# front_ultrasonic_radar.net
KiCad netlist of a schematic drawn in Altium Designer
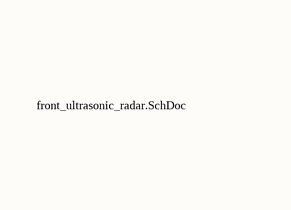
[diagram p0: front_ultrasonic_radar.SchDoc, left]
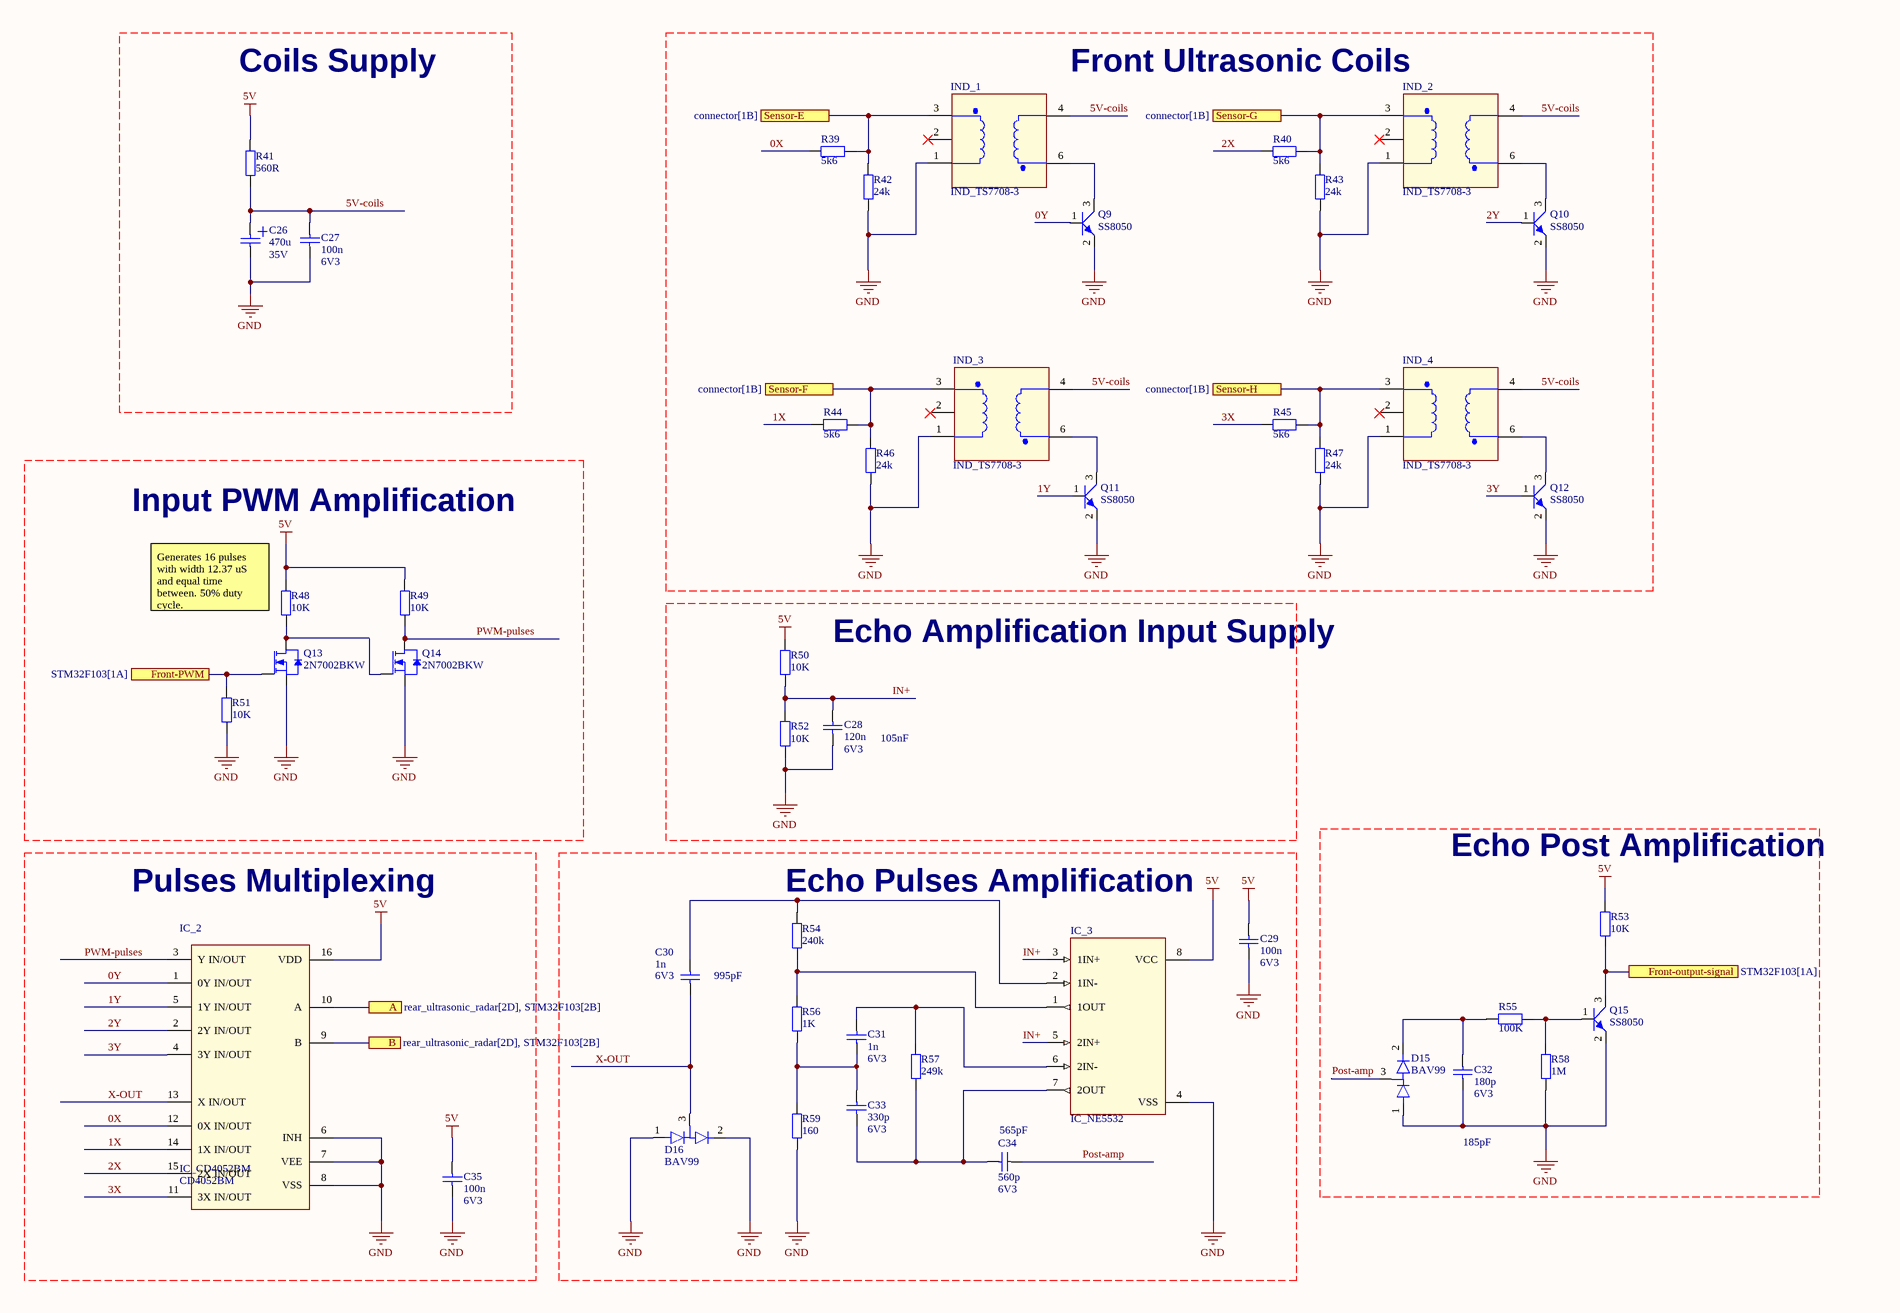
[diagram p1: front_ultrasonic_radar.SchDoc, right]

(export (version "E")
  (design (tool "Eeschema 10.0.6"))
  (components
    (comp (ref "C26")
      (value "CAP_POL")
      (footprint "CAP_Panasonic_EEE-FK1V471SP")
      (description "Aluminium Electrolytic Capacitors - SMD 35volts 470uF SMD AEC-Q200 Reflow Only")
      (fields
        (field (name "VALUE1") "470u")
        (field (name "VALUE2") "35V")
        (field (name "MANUFACTURER") "Panasonic")
      )
      (libsource (lib "DSW_Lib") (part "CAP_POL"))
    )
    (comp (ref "C27")
      (value "CAP")
      (footprint "CAPC2012X88N")
      (description "X7R 10% 0805")
      (fields
        (field (name "VALUE1") "100n")
        (field (name "VALUE2") "6V3")
        (field (name "MANUFACTURER") "KEMET")
      )
      (libsource (lib "DSW_Lib") (part "CAP"))
    )
    (comp (ref "C28")
      (value "CAP")
      (footprint "CAPC2012X88N")
      (description "X7R 10% 0805")
      (fields
        (field (name "VALUE1") "120n")
        (field (name "VALUE2") "6V3")
        (field (name "MANUFACTURER") "KEMET")
      )
      (libsource (lib "DSW_Lib") (part "CAP"))
    )
    (comp (ref "C29")
      (value "CAP")
      (footprint "CAPC2012X88N")
      (description "X7R 10% 0805")
      (fields
        (field (name "VALUE1") "100n")
        (field (name "VALUE2") "6V3")
        (field (name "MANUFACTURER") "KEMET")
      )
      (libsource (lib "DSW_Lib") (part "CAP"))
    )
    (comp (ref "C30")
      (value "CAP")
      (footprint "CAPC2012X88N")
      (description "X7R 10% 0805")
      (fields
        (field (name "VALUE1") "1n")
        (field (name "VALUE2") "6V3")
        (field (name "MANUFACTURER") "KEMET")
      )
      (libsource (lib "DSW_Lib") (part "CAP"))
    )
    (comp (ref "C31")
      (value "CAP")
      (footprint "CAPC2012X88N")
      (description "X7R 10% 0805")
      (fields
        (field (name "VALUE1") "1n")
        (field (name "VALUE2") "6V3")
        (field (name "MANUFACTURER") "KEMET")
      )
      (libsource (lib "DSW_Lib") (part "CAP"))
    )
    (comp (ref "C32")
      (value "CAP")
      (footprint "CAPC2012X88N")
      (description "X7R 10% 0805")
      (fields
        (field (name "VALUE1") "180p")
        (field (name "VALUE2") "6V3")
        (field (name "MANUFACTURER") "KEMET")
      )
      (libsource (lib "DSW_Lib") (part "CAP"))
    )
    (comp (ref "C33")
      (value "CAP")
      (footprint "CAPC2012X88N")
      (description "X7R 10% 0805")
      (fields
        (field (name "VALUE1") "330p")
        (field (name "VALUE2") "6V3")
        (field (name "MANUFACTURER") "KEMET")
      )
      (libsource (lib "DSW_Lib") (part "CAP"))
    )
    (comp (ref "C34")
      (value "CAP")
      (footprint "CAPC2012X88N")
      (description "X7R 10% 0805")
      (fields
        (field (name "VALUE1") "560p")
        (field (name "VALUE2") "6V3")
        (field (name "MANUFACTURER") "KEMET")
      )
      (libsource (lib "DSW_Lib") (part "CAP"))
    )
    (comp (ref "C35")
      (value "CAP")
      (footprint "CAPC2012X88N")
      (description "X7R 10% 0805")
      (fields
        (field (name "VALUE1") "100n")
        (field (name "VALUE2") "6V3")
        (field (name "MANUFACTURER") "KEMET")
      )
      (libsource (lib "DSW_Lib") (part "CAP"))
    )
    (comp (ref "D15")
      (value "High-speed double diode")
      (footprint "DIO_BAV99-SOT23")
      (fields (field (name "VALUE1") "BAV99") (field (name "MANUFACTURER") "Philips"))
      (libsource (lib "DSW_Lib") (part "DIO_BAV99"))
    )
    (comp (ref "D16")
      (value "High-speed double diode")
      (footprint "DIO_BAV99-SOT23")
      (fields (field (name "VALUE1") "BAV99") (field (name "MANUFACTURER") "Philips"))
      (libsource (lib "DSW_Lib") (part "DIO_BAV99"))
    )
    (comp (ref "IC_2")
      (value "IC_CD4052BM")
      (footprint "SOP-16")
      (description "Dual 4-Channel Analog Multiplexer/Demultiplexer")
      (fields (field (name "VALUE1") "CD4052BM") (field (name "MANUFACTURER") "Texas Instruments"))
      (libsource (lib "DSW_Lib") (part "IC_CD4052BM"))
    )
    (comp (ref "IC_3")
      (value "IC_NE5532")
      (description "Dual low-noise operational amplifier ")
      (libsource (lib "IC_NE5532") (part "IC_NE5532"))
    )
    (comp (ref "IND_1")
      (value "IND_TS7708-3")
      (description "12times Amplifying Transformer,IFT Inductors for Ultrasonic Sensors")
      (libsource (lib "IND_TS7708-3") (part "IND_TS7708-3"))
    )
    (comp (ref "IND_2")
      (value "IND_TS7708-3")
      (description "12times Amplifying Transformer,IFT Inductors for Ultrasonic Sensors")
      (libsource (lib "IND_TS7708-3") (part "IND_TS7708-3"))
    )
    (comp (ref "IND_3")
      (value "IND_TS7708-3")
      (description "12times Amplifying Transformer,IFT Inductors for Ultrasonic Sensors")
      (libsource (lib "IND_TS7708-3") (part "IND_TS7708-3"))
    )
    (comp (ref "IND_4")
      (value "IND_TS7708-3")
      (description "12times Amplifying Transformer,IFT Inductors for Ultrasonic Sensors")
      (libsource (lib "IND_TS7708-3") (part "IND_TS7708-3"))
    )
    (comp (ref "Q9")
      (value "TRS_NPN_123")
      (footprint "SOT23")
      (description "Bipolar Transistors - BJT NPN TRANSISTOR 1.5A 40V")
      (fields (field (name "VALUE1") "SS8050") (field (name "MANUFACTURER") "KooChin"))
      (libsource (lib "DSW_Lib") (part "TRS_NPN_123"))
    )
    (comp (ref "Q10")
      (value "TRS_NPN_123")
      (footprint "SOT23")
      (description "Bipolar Transistors - BJT NPN TRANSISTOR 1.5A 40V")
      (fields (field (name "VALUE1") "SS8050") (field (name "MANUFACTURER") "KooChin"))
      (libsource (lib "DSW_Lib") (part "TRS_NPN_123"))
    )
    (comp (ref "Q11")
      (value "TRS_NPN_123")
      (footprint "SOT23")
      (description "Bipolar Transistors - BJT NPN TRANSISTOR 1.5A 40V")
      (fields (field (name "VALUE1") "SS8050") (field (name "MANUFACTURER") "KooChin"))
      (libsource (lib "DSW_Lib") (part "TRS_NPN_123"))
    )
    (comp (ref "Q12")
      (value "TRS_NPN_123")
      (footprint "SOT23")
      (description "Bipolar Transistors - BJT NPN TRANSISTOR 1.5A 40V")
      (fields (field (name "VALUE1") "SS8050") (field (name "MANUFACTURER") "KooChin"))
      (libsource (lib "DSW_Lib") (part "TRS_NPN_123"))
    )
    (comp (ref "Q13")
      (value "TRS_FETN_123")
      (footprint "SOT65P210X110-3N")
      (description "NXP - 2N7002BKW - MOSFET, N CH, 60V, 0.31A, SOT323")
      (fields (field (name "VALUE1") "2N7002BKW") (field (name "MANUFACTURER") "NXP"))
      (libsource (lib "DSW_Lib") (part "TRS_FETN_123"))
    )
    (comp (ref "Q14")
      (value "TRS_FETN_123")
      (footprint "SOT65P210X110-3N")
      (description "NXP - 2N7002BKW - MOSFET, N CH, 60V, 0.31A, SOT323")
      (fields (field (name "VALUE1") "2N7002BKW") (field (name "MANUFACTURER") "NXP"))
      (libsource (lib "DSW_Lib") (part "TRS_FETN_123"))
    )
    (comp (ref "Q15")
      (value "TRS_NPN_123")
      (footprint "SOT23")
      (description "Bipolar Transistors - BJT NPN TRANSISTOR 1.5A 40V")
      (fields (field (name "VALUE1") "SS8050") (field (name "MANUFACTURER") "KooChin"))
      (libsource (lib "DSW_Lib") (part "TRS_NPN_123"))
    )
    (comp (ref "R39")
      (value "RES")
      (footprint "RESC2012X60N")
      (description "RESISTOR, 0805, 5k6, 1%, SMD")
      (fields (field (name "VALUE1") "5k6") (field (name "MANUFACTURER") "Yageo"))
      (libsource (lib "") (part "RES_1"))
    )
    (comp (ref "R40")
      (value "RES")
      (footprint "RESC2012X60N")
      (description "RESISTOR, 0805, 5k6, 1%, SMD")
      (fields (field (name "VALUE1") "5k6") (field (name "MANUFACTURER") "Yageo"))
      (libsource (lib "") (part "RES_1"))
    )
    (comp (ref "R41")
      (value "RES")
      (footprint "RESC2012X60N")
      (description "RESISTOR, 0805, 560R, 1%, SMD")
      (fields (field (name "VALUE1") "560R") (field (name "MANUFACTURER") "Yageo"))
      (libsource (lib "DSW_Lib") (part "RES"))
    )
    (comp (ref "R42")
      (value "RES")
      (footprint "RESC2012X60N")
      (description "RESISTOR, 0805, 24k, 1%, SMD")
      (fields (field (name "VALUE1") "24k") (field (name "MANUFACTURER") "Yageo"))
      (libsource (lib "DSW_Lib") (part "RES"))
    )
    (comp (ref "R43")
      (value "RES")
      (footprint "RESC2012X60N")
      (description "RESISTOR, 0805, 24k, 1%, SMD")
      (fields (field (name "VALUE1") "24k") (field (name "MANUFACTURER") "Yageo"))
      (libsource (lib "DSW_Lib") (part "RES"))
    )
    (comp (ref "R44")
      (value "RES")
      (footprint "RESC2012X60N")
      (description "RESISTOR, 0805, 5k6, 1%, SMD")
      (fields (field (name "VALUE1") "5k6") (field (name "MANUFACTURER") "Yageo"))
      (libsource (lib "") (part "RES_1"))
    )
    (comp (ref "R45")
      (value "RES")
      (footprint "RESC2012X60N")
      (description "RESISTOR, 0805, 5k6, 1%, SMD")
      (fields (field (name "VALUE1") "5k6") (field (name "MANUFACTURER") "Yageo"))
      (libsource (lib "") (part "RES_1"))
    )
    (comp (ref "R46")
      (value "RES")
      (footprint "RESC2012X60N")
      (description "RESISTOR, 0805, 24k, 1%, SMD")
      (fields (field (name "VALUE1") "24k") (field (name "MANUFACTURER") "Yageo"))
      (libsource (lib "DSW_Lib") (part "RES"))
    )
    (comp (ref "R47")
      (value "RES")
      (footprint "RESC2012X60N")
      (description "RESISTOR, 0805, 24k, 1%, SMD")
      (fields (field (name "VALUE1") "24k") (field (name "MANUFACTURER") "Yageo"))
      (libsource (lib "DSW_Lib") (part "RES"))
    )
    (comp (ref "R48")
      (value "RES")
      (footprint "RESC2012X60N")
      (description "RESISTOR, 0805, 10K, 1%, SMD")
      (fields (field (name "VALUE1") "10K") (field (name "MANUFACTURER") "Yageo"))
      (libsource (lib "DSW_Lib") (part "RES"))
    )
    (comp (ref "R49")
      (value "RES")
      (footprint "RESC2012X60N")
      (description "RESISTOR, 0805, 10K, 1%, SMD")
      (fields (field (name "VALUE1") "10K") (field (name "MANUFACTURER") "Yageo"))
      (libsource (lib "DSW_Lib") (part "RES"))
    )
    (comp (ref "R50")
      (value "RES")
      (footprint "RESC2012X60N")
      (description "RESISTOR, 0805, 10K, 1%, SMD")
      (fields (field (name "VALUE1") "10K") (field (name "MANUFACTURER") "Yageo"))
      (libsource (lib "") (part "RES_2"))
    )
    (comp (ref "R51")
      (value "RES")
      (footprint "RESC2012X60N")
      (description "RESISTOR, 0805, 10K, 1%, SMD")
      (fields (field (name "VALUE1") "10K") (field (name "MANUFACTURER") "Yageo"))
      (libsource (lib "DSW_Lib") (part "RES"))
    )
    (comp (ref "R52")
      (value "RES")
      (footprint "RESC2012X60N")
      (description "RESISTOR, 0805, 10K, 1%, SMD")
      (fields (field (name "VALUE1") "10K") (field (name "MANUFACTURER") "Yageo"))
      (libsource (lib "DSW_Lib") (part "RES"))
    )
    (comp (ref "R53")
      (value "RES")
      (footprint "RESC2012X60N")
      (description "RESISTOR, 0805, 10K, 1%, SMD")
      (fields (field (name "VALUE1") "10K") (field (name "MANUFACTURER") "Yageo"))
      (libsource (lib "DSW_Lib") (part "RES"))
    )
    (comp (ref "R54")
      (value "RES")
      (footprint "RESC2012X60N")
      (description "RESISTOR, 0805, 240k, 1%, SMD")
      (fields (field (name "VALUE1") "240k") (field (name "MANUFACTURER") "Yageo"))
      (libsource (lib "") (part "RES_2"))
    )
    (comp (ref "R55")
      (value "RES")
      (footprint "RESC2012X60N")
      (description "RESISTOR, 0805, 100K, 1%, SMD")
      (fields (field (name "VALUE1") "100K") (field (name "MANUFACTURER") "Yageo"))
      (libsource (lib "") (part "RES_3"))
    )
    (comp (ref "R56")
      (value "RES")
      (footprint "RESC2012X60N")
      (description "RESISTOR, 0805, 1K, 1%, SMD")
      (fields (field (name "VALUE1") "1K") (field (name "MANUFACTURER") "Yageo"))
      (libsource (lib "DSW_Lib") (part "RES"))
    )
    (comp (ref "R57")
      (value "RES")
      (footprint "RESC2012X60N")
      (description "RESISTOR, 0805, 249k, 1%, SMD")
      (fields (field (name "VALUE1") "249k") (field (name "MANUFACTURER") "Yageo"))
      (libsource (lib "") (part "RES_2"))
    )
    (comp (ref "R58")
      (value "RES")
      (footprint "RESC2012X60N")
      (description "RESISTOR, 0805, 1M, 1%, SMD")
      (fields (field (name "VALUE1") "1M") (field (name "MANUFACTURER") "Yageo"))
      (libsource (lib "DSW_Lib") (part "RES"))
    )
    (comp (ref "R59")
      (value "RES")
      (footprint "RESC2012X60N")
      (description "RESISTOR, 0805, 160, 1%, SMD")
      (fields (field (name "VALUE1") "160") (field (name "MANUFACTURER") "Yageo"))
      (libsource (lib "DSW_Lib") (part "RES"))
    )
  )
  (nets
    (net (code "1") (name "/0X") (class "Default")
      (node (ref "IC_2") (pin "12") (pinfunction "0X_IN/OUT_12") (pintype "passive"))
      (node (ref "R39") (pin "2") (pinfunction "2_2") (pintype "passive"))
    )
    (net (code "2") (name "/0Y") (class "Default")
      (node (ref "IC_2") (pin "1") (pinfunction "0Y_IN/OUT_1") (pintype "passive"))
      (node (ref "Q9") (pin "1") (pinfunction "B_1") (pintype "passive"))
    )
    (net (code "3") (name "/1X") (class "Default")
      (node (ref "IC_2") (pin "14") (pinfunction "1X_IN/OUT_14") (pintype "passive"))
      (node (ref "R44") (pin "2") (pinfunction "2_2") (pintype "passive"))
    )
    (net (code "4") (name "/1Y") (class "Default")
      (node (ref "IC_2") (pin "5") (pinfunction "1Y_IN/OUT_5") (pintype "passive"))
      (node (ref "Q11") (pin "1") (pinfunction "B_1") (pintype "passive"))
    )
    (net (code "5") (name "/2X") (class "Default")
      (node (ref "IC_2") (pin "15") (pinfunction "2X_IN/OUT_15") (pintype "passive"))
      (node (ref "R40") (pin "2") (pinfunction "2_2") (pintype "passive"))
    )
    (net (code "6") (name "/2Y") (class "Default")
      (node (ref "IC_2") (pin "2") (pinfunction "2Y_IN/OUT_2") (pintype "passive"))
      (node (ref "Q10") (pin "1") (pinfunction "B_1") (pintype "passive"))
    )
    (net (code "7") (name "/3X") (class "Default")
      (node (ref "IC_2") (pin "11") (pinfunction "3X_IN/OUT_11") (pintype "passive"))
      (node (ref "R45") (pin "2") (pinfunction "2_2") (pintype "passive"))
    )
    (net (code "8") (name "/3Y") (class "Default")
      (node (ref "IC_2") (pin "4") (pinfunction "3Y_IN/OUT_4") (pintype "passive"))
      (node (ref "Q12") (pin "1") (pinfunction "B_1") (pintype "passive"))
    )
    (net (code "9") (name "/5V-coils") (class "Default")
      (node (ref "C26") (pin "1") (pinfunction "1_1") (pintype "passive"))
      (node (ref "C27") (pin "2") (pinfunction "2_2") (pintype "passive"))
      (node (ref "IND_1") (pin "4") (pinfunction "4_4") (pintype "passive"))
      (node (ref "IND_2") (pin "4") (pinfunction "4_4") (pintype "passive"))
      (node (ref "IND_3") (pin "4") (pinfunction "4_4") (pintype "passive"))
      (node (ref "IND_4") (pin "4") (pinfunction "4_4") (pintype "passive"))
      (node (ref "R41") (pin "1") (pinfunction "1_1") (pintype "passive"))
    )
    (net (code "10") (name "/A") (class "Default")
      (node (ref "IC_2") (pin "10") (pinfunction "A_10") (pintype "passive"))
    )
    (net (code "11") (name "/B") (class "Default")
      (node (ref "IC_2") (pin "9") (pinfunction "B_9") (pintype "passive"))
    )
    (net (code "12") (name "/Front-PWM") (class "Default")
      (node (ref "Q13") (pin "1") (pinfunction "G_1") (pintype "passive"))
      (node (ref "R51") (pin "2") (pinfunction "2_2") (pintype "passive"))
    )
    (net (code "13") (name "/Front-output-signal") (class "Default")
      (node (ref "Q15") (pin "3") (pinfunction "C_3") (pintype "passive"))
      (node (ref "R53") (pin "1") (pinfunction "1_1") (pintype "passive"))
    )
    (net (code "14") (name "/IN+") (class "Default")
      (node (ref "C28") (pin "2") (pinfunction "2_2") (pintype "passive"))
      (node (ref "IC_3") (pin "3") (pinfunction "1IN+_3") (pintype "input"))
      (node (ref "IC_3") (pin "5") (pinfunction "2IN+_5") (pintype "input"))
      (node (ref "R50") (pin "2") (pinfunction "2_2") (pintype "passive"))
      (node (ref "R52") (pin "2") (pinfunction "2_2") (pintype "passive"))
    )
    (net (code "15") (name "/PWM-pulses") (class "Default")
      (node (ref "IC_2") (pin "3") (pinfunction "Y_IN/OUT_3") (pintype "passive"))
      (node (ref "Q14") (pin "3") (pinfunction "D_3") (pintype "passive"))
      (node (ref "R49") (pin "1") (pinfunction "1_1") (pintype "passive"))
    )
    (net (code "16") (name "/Post-amp") (class "Default")
      (node (ref "C34") (pin "1") (pinfunction "1_1") (pintype "passive"))
      (node (ref "D15") (pin "3") (pinfunction "K_3") (pintype "passive"))
    )
    (net (code "17") (name "/Sensor-E") (class "Default")
      (node (ref "IND_1") (pin "3") (pinfunction "S2_3") (pintype "passive"))
      (node (ref "R39") (pin "1") (pinfunction "1_1") (pintype "passive"))
      (node (ref "R42") (pin "2") (pinfunction "2_2") (pintype "passive"))
    )
    (net (code "18") (name "/Sensor-F") (class "Default")
      (node (ref "IND_3") (pin "3") (pinfunction "S2_3") (pintype "passive"))
      (node (ref "R44") (pin "1") (pinfunction "1_1") (pintype "passive"))
      (node (ref "R46") (pin "2") (pinfunction "2_2") (pintype "passive"))
    )
    (net (code "19") (name "/Sensor-G") (class "Default")
      (node (ref "IND_2") (pin "3") (pinfunction "S2_3") (pintype "passive"))
      (node (ref "R40") (pin "1") (pinfunction "1_1") (pintype "passive"))
      (node (ref "R43") (pin "2") (pinfunction "2_2") (pintype "passive"))
    )
    (net (code "20") (name "/Sensor-H") (class "Default")
      (node (ref "IND_4") (pin "3") (pinfunction "S2_3") (pintype "passive"))
      (node (ref "R45") (pin "1") (pinfunction "1_1") (pintype "passive"))
      (node (ref "R47") (pin "2") (pinfunction "2_2") (pintype "passive"))
    )
    (net (code "21") (name "/X-OUT") (class "Default")
      (node (ref "C30") (pin "1") (pinfunction "1_1") (pintype "passive"))
      (node (ref "D16") (pin "3") (pinfunction "K_3") (pintype "passive"))
      (node (ref "IC_2") (pin "13") (pinfunction "X_IN/OUT_13") (pintype "passive"))
    )
    (net (code "22") (name "5V") (class "Default")
      (node (ref "C29") (pin "2") (pinfunction "2_2") (pintype "passive"))
      (node (ref "C35") (pin "2") (pinfunction "2_2") (pintype "passive"))
      (node (ref "IC_2") (pin "16") (pinfunction "VDD_16") (pintype "passive"))
      (node (ref "IC_3") (pin "8") (pinfunction "VCC_8") (pintype "power_in"))
      (node (ref "R41") (pin "2") (pinfunction "2_2") (pintype "passive"))
      (node (ref "R48") (pin "2") (pinfunction "2_2") (pintype "passive"))
      (node (ref "R49") (pin "2") (pinfunction "2_2") (pintype "passive"))
      (node (ref "R50") (pin "1") (pinfunction "1_1") (pintype "passive"))
      (node (ref "R53") (pin "2") (pinfunction "2_2") (pintype "passive"))
    )
    (net (code "23") (name "GND") (class "Default")
      (node (ref "C26") (pin "2") (pinfunction "2_2") (pintype "passive"))
      (node (ref "C27") (pin "1") (pinfunction "1_1") (pintype "passive"))
      (node (ref "C28") (pin "1") (pinfunction "1_1") (pintype "passive"))
      (node (ref "C29") (pin "1") (pinfunction "1_1") (pintype "passive"))
      (node (ref "C32") (pin "1") (pinfunction "1_1") (pintype "passive"))
      (node (ref "C35") (pin "1") (pinfunction "1_1") (pintype "passive"))
      (node (ref "D15") (pin "1") (pinfunction "A1_1") (pintype "passive"))
      (node (ref "D16") (pin "1") (pinfunction "A1_1") (pintype "passive"))
      (node (ref "D16") (pin "2") (pinfunction "A2_2") (pintype "passive"))
      (node (ref "IC_2") (pin "6") (pinfunction "INH_6") (pintype "passive"))
      (node (ref "IC_2") (pin "7") (pinfunction "VEE_7") (pintype "passive"))
      (node (ref "IC_2") (pin "8") (pinfunction "VSS_8") (pintype "passive"))
      (node (ref "IC_3") (pin "4") (pinfunction "VSS_4") (pintype "power_in"))
      (node (ref "IND_1") (pin "1") (pinfunction "1_1") (pintype "passive"))
      (node (ref "IND_2") (pin "1") (pinfunction "1_1") (pintype "passive"))
      (node (ref "IND_3") (pin "1") (pinfunction "1_1") (pintype "passive"))
      (node (ref "IND_4") (pin "1") (pinfunction "1_1") (pintype "passive"))
      (node (ref "Q10") (pin "2") (pinfunction "E_2") (pintype "passive"))
      (node (ref "Q11") (pin "2") (pinfunction "E_2") (pintype "passive"))
      (node (ref "Q12") (pin "2") (pinfunction "E_2") (pintype "passive"))
      (node (ref "Q13") (pin "2") (pinfunction "S_2") (pintype "passive"))
      (node (ref "Q14") (pin "2") (pinfunction "S_2") (pintype "passive"))
      (node (ref "Q15") (pin "2") (pinfunction "E_2") (pintype "passive"))
      (node (ref "Q9") (pin "2") (pinfunction "E_2") (pintype "passive"))
      (node (ref "R42") (pin "1") (pinfunction "1_1") (pintype "passive"))
      (node (ref "R43") (pin "1") (pinfunction "1_1") (pintype "passive"))
      (node (ref "R46") (pin "1") (pinfunction "1_1") (pintype "passive"))
      (node (ref "R47") (pin "1") (pinfunction "1_1") (pintype "passive"))
      (node (ref "R51") (pin "1") (pinfunction "1_1") (pintype "passive"))
      (node (ref "R52") (pin "1") (pinfunction "1_1") (pintype "passive"))
      (node (ref "R58") (pin "1") (pinfunction "1_1") (pintype "passive"))
      (node (ref "R59") (pin "1") (pinfunction "1_1") (pintype "passive"))
    )
    (net (code "24") (name "Net-(C31-Pad2)") (class "Default")
      (node (ref "C31") (pin "2") (pinfunction "2_2") (pintype "passive"))
      (node (ref "C33") (pin "2") (pinfunction "2_2") (pintype "passive"))
      (node (ref "R56") (pin "1") (pinfunction "1_1") (pintype "passive"))
      (node (ref "R59") (pin "2") (pinfunction "2_2") (pintype "passive"))
    )
    (net (code "25") (name "Net-(D15-A2)") (class "Default")
      (node (ref "C32") (pin "2") (pinfunction "2_2") (pintype "passive"))
      (node (ref "D15") (pin "2") (pinfunction "A2_2") (pintype "passive"))
      (node (ref "R55") (pin "1") (pinfunction "1_1") (pintype "passive"))
    )
    (net (code "26") (name "Net-(IC_3-1IN-)") (class "Default")
      (node (ref "C30") (pin "2") (pinfunction "2_2") (pintype "passive"))
      (node (ref "IC_3") (pin "2") (pinfunction "1IN-_2") (pintype "input"))
      (node (ref "R54") (pin "1") (pinfunction "1_1") (pintype "passive"))
    )
    (net (code "27") (name "Net-(IC_3-1OUT)") (class "Default")
      (node (ref "IC_3") (pin "1") (pinfunction "1OUT_1") (pintype "output"))
      (node (ref "R54") (pin "2") (pinfunction "2_2") (pintype "passive"))
      (node (ref "R56") (pin "2") (pinfunction "2_2") (pintype "passive"))
    )
    (net (code "28") (name "Net-(IC_3-2IN-)") (class "Default")
      (node (ref "C31") (pin "1") (pinfunction "1_1") (pintype "passive"))
      (node (ref "IC_3") (pin "6") (pinfunction "2IN-_6") (pintype "input"))
      (node (ref "R57") (pin "1") (pinfunction "1_1") (pintype "passive"))
    )
    (net (code "29") (name "Net-(IC_3-2OUT)") (class "Default")
      (node (ref "C33") (pin "1") (pinfunction "1_1") (pintype "passive"))
      (node (ref "C34") (pin "2") (pinfunction "2_2") (pintype "passive"))
      (node (ref "IC_3") (pin "7") (pinfunction "2OUT_7") (pintype "output"))
      (node (ref "R57") (pin "2") (pinfunction "2_2") (pintype "passive"))
    )
    (net (code "30") (name "Net-(IND_1-S1)") (class "Default")
      (node (ref "IND_1") (pin "6") (pinfunction "S1_6") (pintype "passive"))
      (node (ref "Q9") (pin "3") (pinfunction "C_3") (pintype "passive"))
    )
    (net (code "31") (name "Net-(IND_2-S1)") (class "Default")
      (node (ref "IND_2") (pin "6") (pinfunction "S1_6") (pintype "passive"))
      (node (ref "Q10") (pin "3") (pinfunction "C_3") (pintype "passive"))
    )
    (net (code "32") (name "Net-(IND_3-S1)") (class "Default")
      (node (ref "IND_3") (pin "6") (pinfunction "S1_6") (pintype "passive"))
      (node (ref "Q11") (pin "3") (pinfunction "C_3") (pintype "passive"))
    )
    (net (code "33") (name "Net-(IND_4-S1)") (class "Default")
      (node (ref "IND_4") (pin "6") (pinfunction "S1_6") (pintype "passive"))
      (node (ref "Q12") (pin "3") (pinfunction "C_3") (pintype "passive"))
    )
    (net (code "34") (name "Net-(Q13-D)") (class "Default")
      (node (ref "Q13") (pin "3") (pinfunction "D_3") (pintype "passive"))
      (node (ref "Q14") (pin "1") (pinfunction "G_1") (pintype "passive"))
      (node (ref "R48") (pin "1") (pinfunction "1_1") (pintype "passive"))
    )
    (net (code "35") (name "Net-(Q15-B)") (class "Default")
      (node (ref "Q15") (pin "1") (pinfunction "B_1") (pintype "passive"))
      (node (ref "R55") (pin "2") (pinfunction "2_2") (pintype "passive"))
      (node (ref "R58") (pin "2") (pinfunction "2_2") (pintype "passive"))
    )
    (net (code "36") (name "unconnected-(IND_1-Pad2)") (class "Default")
      (node (ref "IND_1") (pin "2") (pinfunction "2_2") (pintype "passive+no_connect"))
    )
    (net (code "37") (name "unconnected-(IND_2-Pad2)") (class "Default")
      (node (ref "IND_2") (pin "2") (pinfunction "2_2") (pintype "passive+no_connect"))
    )
    (net (code "38") (name "unconnected-(IND_3-Pad2)") (class "Default")
      (node (ref "IND_3") (pin "2") (pinfunction "2_2") (pintype "passive+no_connect"))
    )
    (net (code "39") (name "unconnected-(IND_4-Pad2)") (class "Default")
      (node (ref "IND_4") (pin "2") (pinfunction "2_2") (pintype "passive+no_connect"))
    )
  )
)
